# Y2.net
KiCad netlist of a schematic drawn in Altium Designer
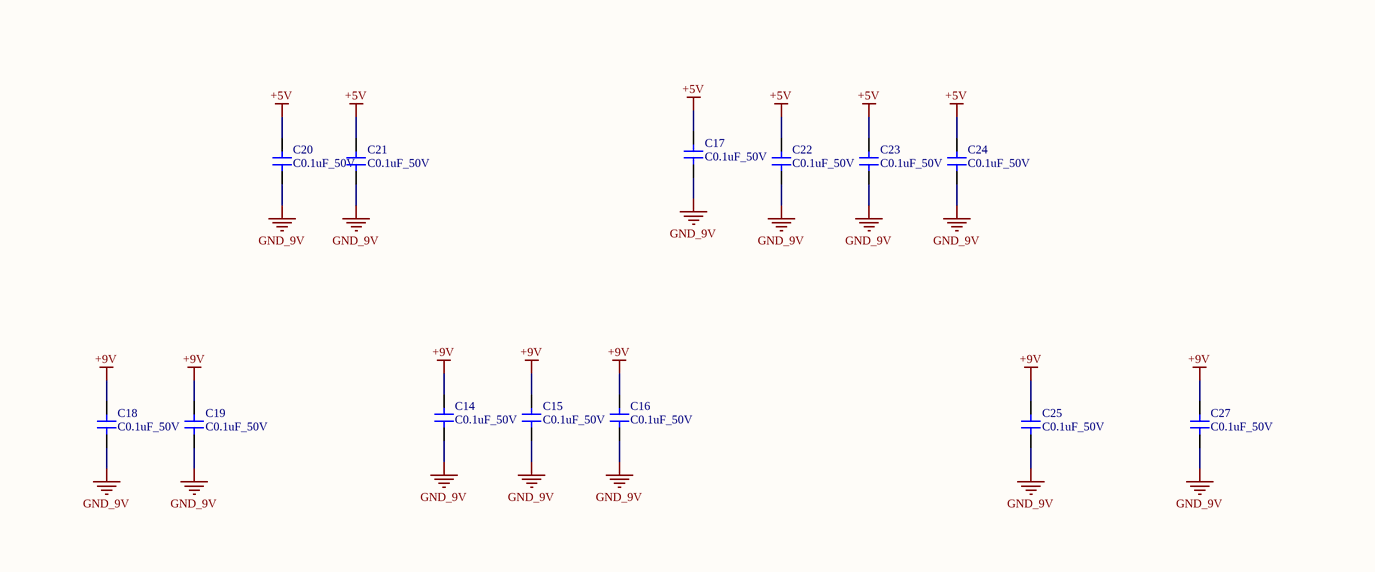
[diagram p0: Y2.SchDoc, top left]
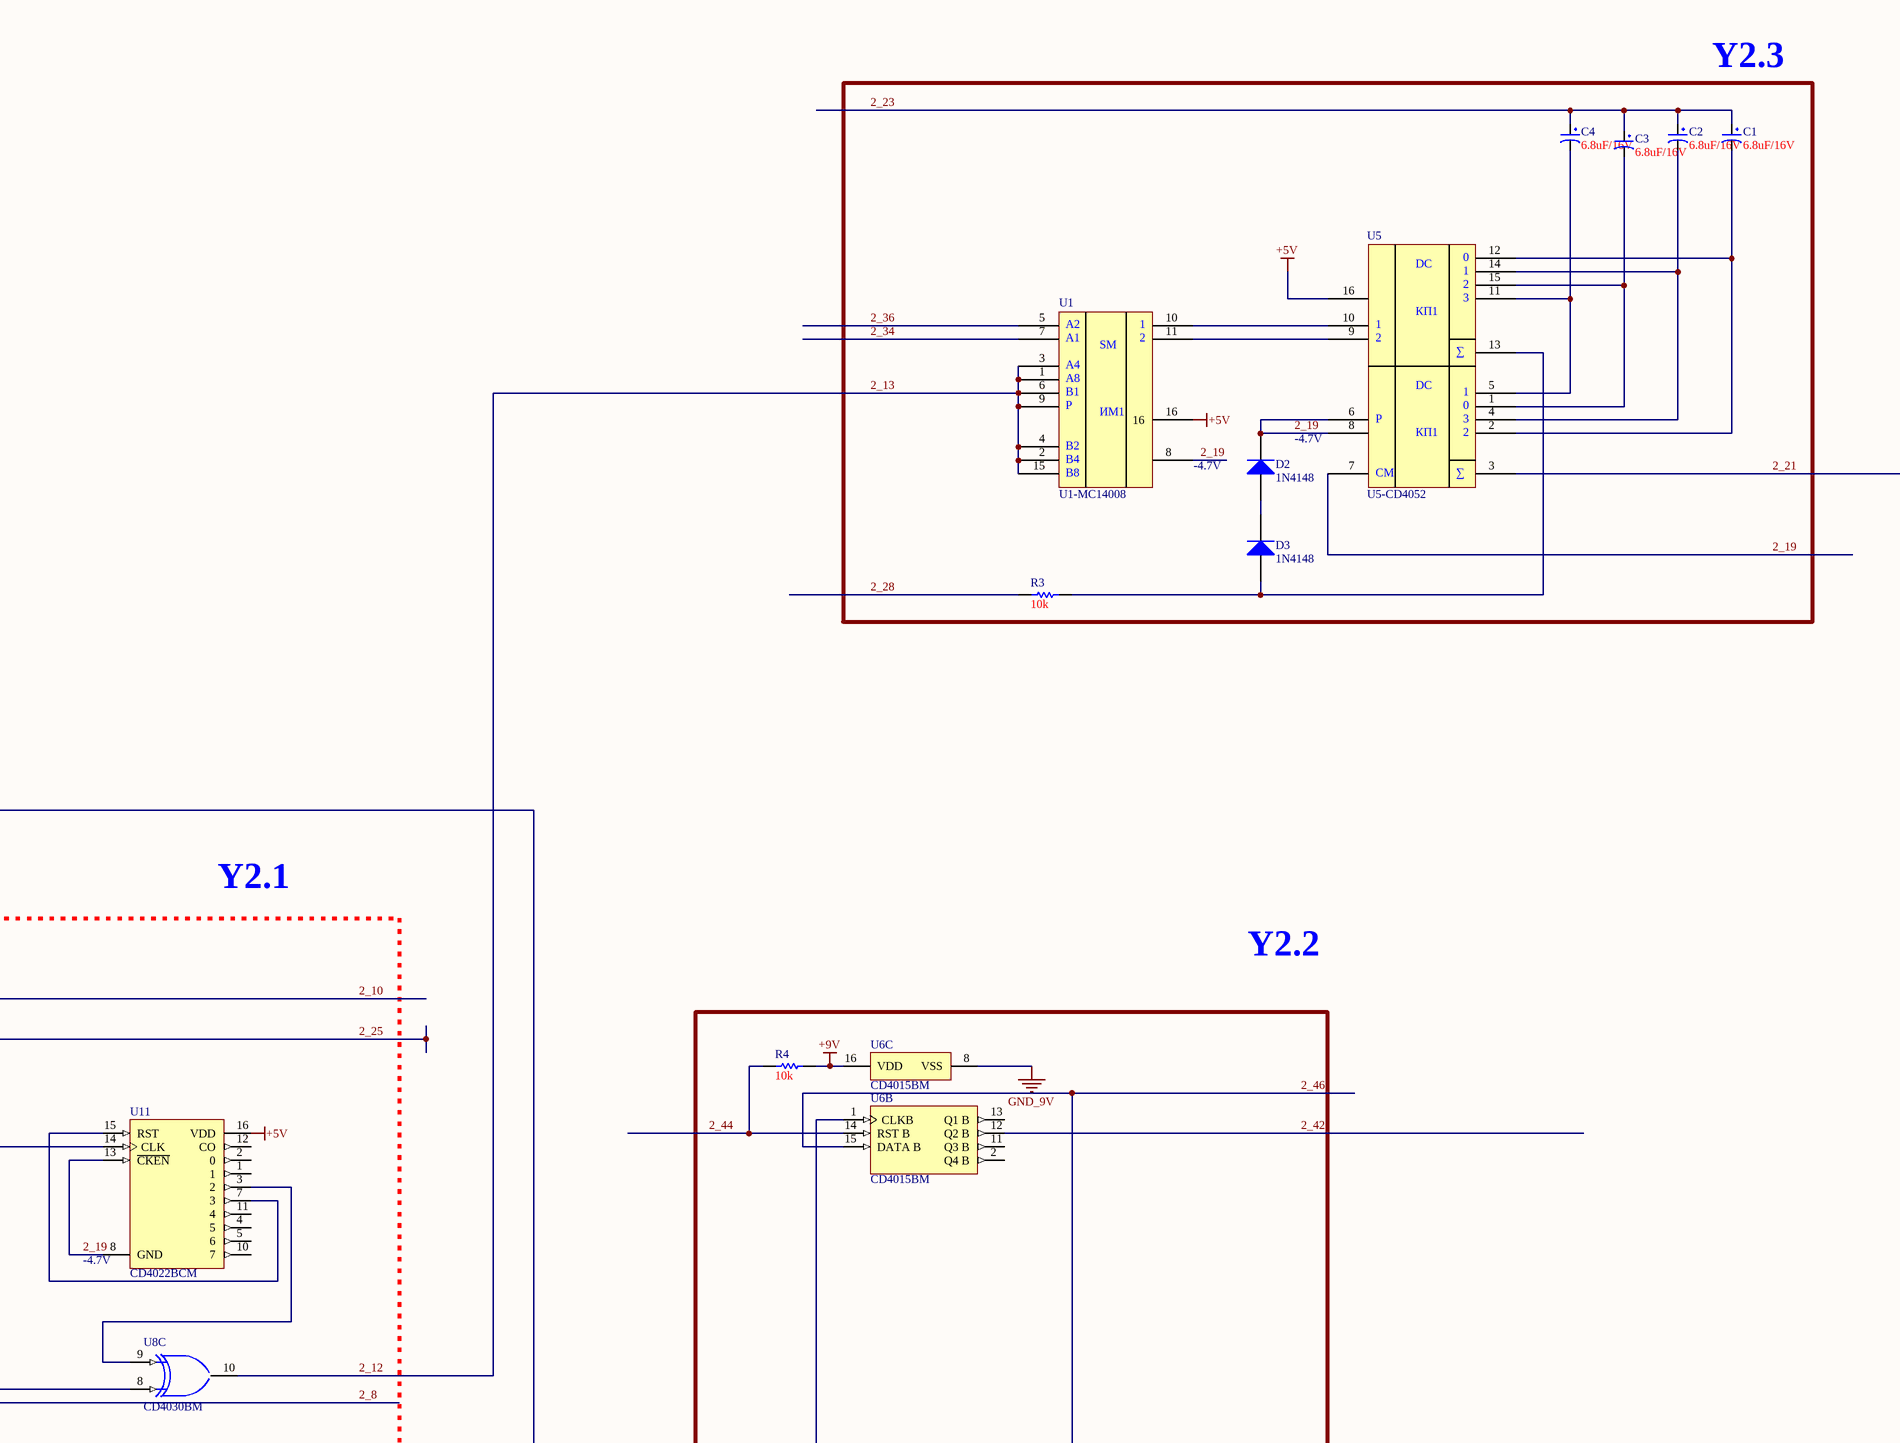
[diagram p1: Y2.SchDoc, top right]
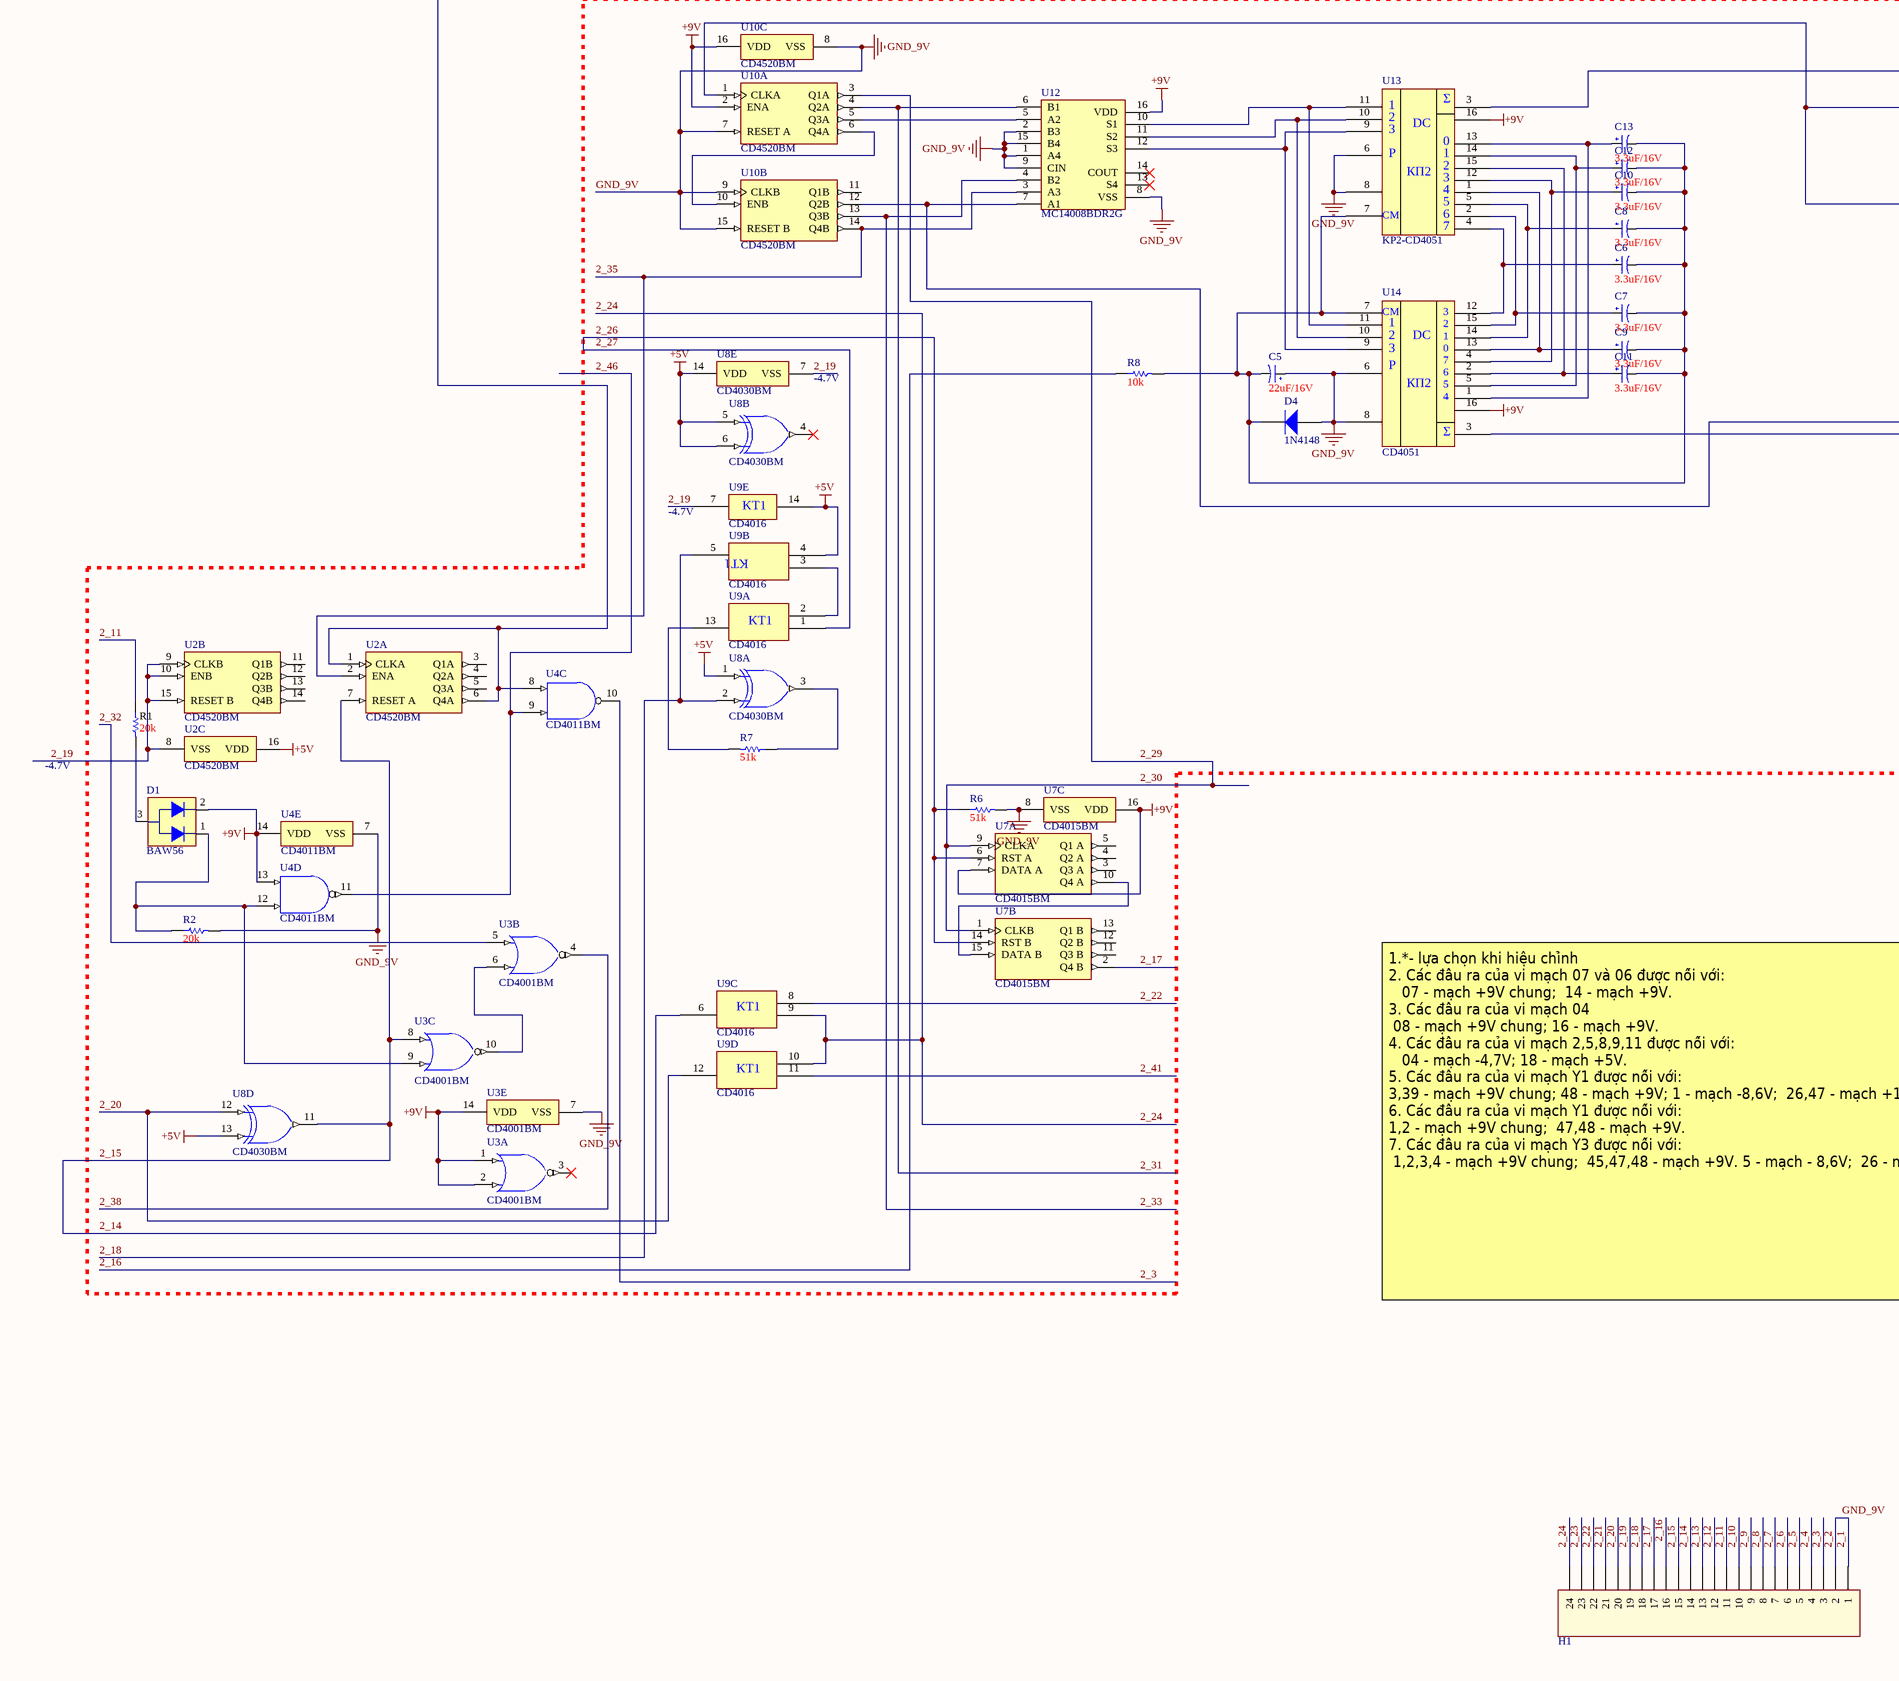
[diagram p2: Y2.SchDoc, bottom left]
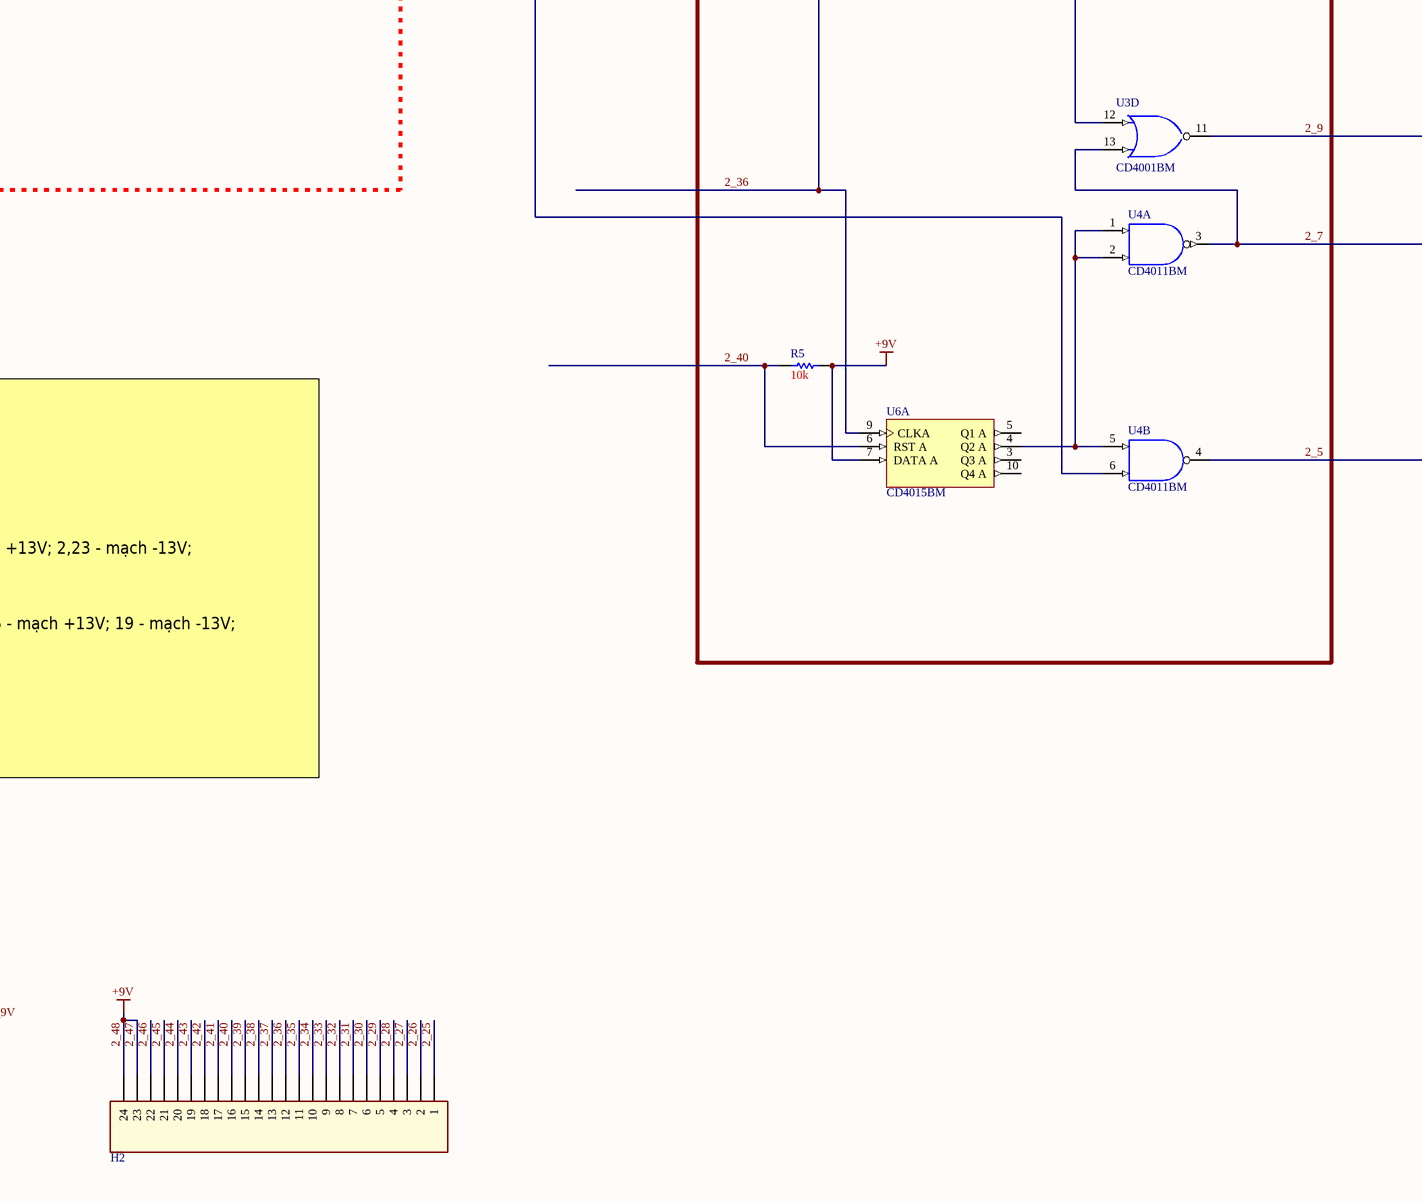
[diagram p3: Y2.SchDoc, bottom right]

(export (version "E")
  (design (tool "Eeschema 10.0.6"))
  (components
    (comp (ref "C1")
      (value "6.8uF/16V")
      (footprint "3216")
      (description "C 47uF/50V , 220uF/16V")
      (libsource (lib "syhaunguyen") (part "CP2"))
    )
    (comp (ref "C2")
      (value "6.8uF/16V")
      (footprint "3216")
      (description "C 47uF/50V , 220uF/16V")
      (libsource (lib "syhaunguyen") (part "CP2"))
    )
    (comp (ref "C3")
      (value "6.8uF/16V")
      (footprint "3216")
      (description "C 47uF/50V , 220uF/16V")
      (libsource (lib "syhaunguyen") (part "CP2"))
    )
    (comp (ref "C4")
      (value "6.8uF/16V")
      (footprint "3216")
      (description "C 47uF/50V , 220uF/16V")
      (libsource (lib "syhaunguyen") (part "CP2"))
    )
    (comp (ref "C5")
      (value "22uF/16V")
      (footprint "3528")
      (description "Cap P  0,1uF < 22uF , 16 - 50V")
      (libsource (lib "syhaunguyen") (part "CP1"))
    )
    (comp (ref "C6")
      (value "3.3uF/16V")
      (footprint "3216")
      (description "Cap P  0,1uF < 22uF , 16 - 50V")
      (libsource (lib "syhaunguyen") (part "CP1"))
    )
    (comp (ref "C7")
      (value "3.3uF/16V")
      (footprint "3216")
      (description "Cap P  0,1uF < 22uF , 16 - 50V")
      (libsource (lib "syhaunguyen") (part "CP1"))
    )
    (comp (ref "C8")
      (value "3.3uF/16V")
      (footprint "3216")
      (description "Cap P  0,1uF < 22uF , 16 - 50V")
      (libsource (lib "syhaunguyen") (part "CP1"))
    )
    (comp (ref "C9")
      (value "3.3uF/16V")
      (footprint "3216")
      (description "Cap P  0,1uF < 22uF , 16 - 50V")
      (libsource (lib "syhaunguyen") (part "CP1"))
    )
    (comp (ref "C10")
      (value "3.3uF/16V")
      (footprint "3216")
      (description "Cap P  0,1uF < 22uF , 16 - 50V")
      (libsource (lib "syhaunguyen") (part "CP1"))
    )
    (comp (ref "C11")
      (value "3.3uF/16V")
      (footprint "3216")
      (description "Cap P  0,1uF < 22uF , 16 - 50V")
      (libsource (lib "syhaunguyen") (part "CP1"))
    )
    (comp (ref "C12")
      (value "3.3uF/16V")
      (footprint "3216")
      (description "Cap P  0,1uF < 22uF , 16 - 50V")
      (libsource (lib "syhaunguyen") (part "CP1"))
    )
    (comp (ref "C13")
      (value "3.3uF/16V")
      (footprint "3216")
      (description "Cap P  0,1uF < 22uF , 16 - 50V")
      (libsource (lib "syhaunguyen") (part "CP1"))
    )
    (comp (ref "C14")
      (value "C0.1uF_50V")
      (footprint "Masterit1805:C0805")
      (libsource (lib "AMK") (part "C0.1uF_50V"))
    )
    (comp (ref "C15")
      (value "C0.1uF_50V")
      (footprint "Masterit1805:C0805")
      (libsource (lib "AMK") (part "C0.1uF_50V"))
    )
    (comp (ref "C16")
      (value "C0.1uF_50V")
      (footprint "Masterit1805:C0805")
      (libsource (lib "AMK") (part "C0.1uF_50V"))
    )
    (comp (ref "C17")
      (value "C0.1uF_50V")
      (footprint "Masterit1805:C0805")
      (libsource (lib "AMK") (part "C0.1uF_50V"))
    )
    (comp (ref "C18")
      (value "C0.1uF_50V")
      (footprint "Masterit1805:C0805")
      (libsource (lib "AMK") (part "C0.1uF_50V"))
    )
    (comp (ref "C19")
      (value "C0.1uF_50V")
      (footprint "Masterit1805:C0805")
      (libsource (lib "AMK") (part "C0.1uF_50V"))
    )
    (comp (ref "C20")
      (value "C0.1uF_50V")
      (footprint "Masterit1805:C0805")
      (libsource (lib "AMK") (part "C0.1uF_50V"))
    )
    (comp (ref "C21")
      (value "C0.1uF_50V")
      (footprint "Masterit1805:C0805")
      (libsource (lib "AMK") (part "C0.1uF_50V"))
    )
    (comp (ref "C22")
      (value "C0.1uF_50V")
      (footprint "Masterit1805:C0805")
      (libsource (lib "AMK") (part "C0.1uF_50V"))
    )
    (comp (ref "C23")
      (value "C0.1uF_50V")
      (footprint "Masterit1805:C0805")
      (libsource (lib "AMK") (part "C0.1uF_50V"))
    )
    (comp (ref "C24")
      (value "C0.1uF_50V")
      (footprint "Masterit1805:C0805")
      (libsource (lib "AMK") (part "C0.1uF_50V"))
    )
    (comp (ref "C25")
      (value "C0.1uF_50V")
      (footprint "Masterit1805:C0805")
      (libsource (lib "AMK") (part "C0.1uF_50V"))
    )
    (comp (ref "C27")
      (value "C0.1uF_50V")
      (footprint "Masterit1805:C0805")
      (libsource (lib "AMK") (part "C0.1uF_50V"))
    )
    (comp (ref "D1") (value "BAW56") (footprint "sot-23") (libsource (lib "27V-30A") (part "UF3")))
    (comp (ref "D2")
      (value "1N4148")
      (footprint "SOD123")
      (description "Dán")
      (libsource (lib "Altium_Lib_by_KhueNguyenCreator") (part "Diode S4"))
    )
    (comp (ref "D3")
      (value "1N4148")
      (footprint "SOD123")
      (description "Dán")
      (libsource (lib "Altium_Lib_by_KhueNguyenCreator") (part "Diode S4"))
    )
    (comp (ref "D4")
      (value "1N4148")
      (footprint "SOD123")
      (description "Dán")
      (libsource (lib "Altium_Lib_by_KhueNguyenCreator") (part "Diode S4"))
    )
    (comp (ref "H1")
      (value "Header 24")
      (footprint "header 24")
      (libsource (lib "LIB_EMBEDDED1805") (part "Header 24"))
    )
    (comp (ref "H2")
      (value "Header 24")
      (footprint "header 24")
      (libsource (lib "LIB_EMBEDDED1805") (part "Header 24"))
    )
    (comp (ref "R1")
      (value "20k")
      (footprint "R0805")
      (description "Standard resistor")
      (fields (field (name "ASID PART NUMBER") "Res-AS"))
      (libsource (lib "Mylib+Rev+4") (part "Res"))
    )
    (comp (ref "R2")
      (value "20k")
      (footprint "R0805")
      (description "Standard resistor")
      (fields (field (name "ASID PART NUMBER") "Res-AS"))
      (libsource (lib "Mylib+Rev+4") (part "Res"))
    )
    (comp (ref "R3")
      (value "10k")
      (footprint "Masterit1805:C0805")
      (description "Standard resistor")
      (fields (field (name "ASID PART NUMBER") "Res-AS"))
      (libsource (lib "Mylib+Rev+4") (part "Res"))
    )
    (comp (ref "R4")
      (value "10k")
      (footprint "R0805")
      (description "Standard resistor")
      (fields (field (name "ASID PART NUMBER") "Res-AS"))
      (libsource (lib "Mylib+Rev+4") (part "Res"))
    )
    (comp (ref "R5")
      (value "10k")
      (footprint "R0805")
      (description "Standard resistor")
      (fields (field (name "ASID PART NUMBER") "Res-AS"))
      (libsource (lib "Mylib+Rev+4") (part "Res"))
    )
    (comp (ref "R6")
      (value "51k")
      (footprint "R0805")
      (description "Standard resistor")
      (fields (field (name "ASID PART NUMBER") "Res-AS"))
      (libsource (lib "Mylib+Rev+4") (part "Res"))
    )
    (comp (ref "R7")
      (value "51k")
      (footprint "Masterit1805:C0805")
      (description "Standard resistor")
      (fields (field (name "ASID PART NUMBER") "Res-AS"))
      (libsource (lib "Mylib+Rev+4") (part "Res"))
    )
    (comp (ref "R8")
      (value "10k")
      (footprint "1206")
      (description "Standard resistor")
      (fields (field (name "ASID PART NUMBER") "Res-AS"))
      (libsource (lib "Mylib+Rev+4") (part "Res"))
    )
    (comp (ref "U1")
      (value "U1-MC14008")
      (footprint "soic16n")
      (libsource (lib "LIB_OF_PHONG") (part "U1-MC14008"))
    )
    (comp (ref "U2")
      (value "CD4520BM")
      (footprint "D0016A_N")
      (description "CMOS Dual Binary Up-Counter, D0016A, TUBE")
      (fields
        (field (name "GENERIC PART NUMBER") "CD4520B")
        (field (name "MANUFACTURER") "Texas Instruments")
      )
      (libsource (lib "TI_Logic_Specialty_Logic") (part "CD4520BM"))
    )
    (comp (ref "U3")
      (value "CD4001BM")
      (footprint "D0014A_N")
      (description "CMOS Quad 2-Input NOR Gate, D0014A, TUBE")
      (fields
        (field (name "GENERIC PART NUMBER") "CD4001B")
        (field (name "MANUFACTURER") "Texas Instruments")
      )
      (libsource (lib "TI_Logic_Gate") (part "CD4001BM"))
    )
    (comp (ref "U4")
      (value "CD4011BM")
      (footprint "D0014A_N")
      (description "CMOS Quad 2-Input NAND Gate, D0014A, TUBE")
      (fields
        (field (name "GENERIC PART NUMBER") "CD4011B")
        (field (name "MANUFACTURER") "Texas Instruments")
      )
      (libsource (lib "TI_Logic_Gate") (part "CD4011BM"))
    )
    (comp (ref "U5")
      (value "U5-CD4052")
      (footprint "soic16n")
      (libsource (lib "LIB_OF_PHONG") (part "U5-CD4052"))
    )
    (comp (ref "U6")
      (value "CD4015BM")
      (footprint "D0016A_N")
      (description "CMOS Dual 4-Stage Static Shift Register, D0016A, TUBE")
      (fields
        (field (name "GENERIC PART NUMBER") "CD4015B")
        (field (name "MANUFACTURER") "Texas Instruments")
      )
      (libsource (lib "TI_Logic_Flip-Flop,Latch,Register") (part "CD4015BM"))
    )
    (comp (ref "U7")
      (value "CD4015BM")
      (footprint "D0016A_N")
      (description "CMOS Dual 4-Stage Static Shift Register, D0016A, TUBE")
      (fields
        (field (name "GENERIC PART NUMBER") "CD4015B")
        (field (name "MANUFACTURER") "Texas Instruments")
      )
      (libsource (lib "") (part "CD4015BM_1"))
    )
    (comp (ref "U8")
      (value "CD4030BM")
      (footprint "D0014A_N")
      (description "CMOS Quad Exclusive-OR Gate, D0014A, TUBE")
      (fields
        (field (name "GENERIC PART NUMBER") "CD4030B")
        (field (name "MANUFACTURER") "Texas Instruments")
      )
      (libsource (lib "TI_Logic_Gate") (part "CD4030BM"))
    )
    (comp (ref "U9") (value "CD4016") (footprint "SOIC14") (libsource (lib "LIB_OF_PHONG") (part "CD4016")))
    (comp (ref "U10")
      (value "CD4520BM")
      (footprint "D0016A_N")
      (description "CMOS Dual Binary Up-Counter, D0016A, TUBE")
      (fields
        (field (name "GENERIC PART NUMBER") "CD4520B")
        (field (name "MANUFACTURER") "Texas Instruments")
      )
      (libsource (lib "") (part "CD4520BM_1"))
    )
    (comp (ref "U11")
      (value "CD4022BCM")
      (footprint "SOP16")
      (description "Divide by 8 Counter/Divider with 8 Decoded Outputs")
      (fields (field (name "PUBLISHER") "Altium Limited"))
      (libsource (lib "FSC Logic Counter") (part "CD4022BCM"))
    )
    (comp (ref "U12")
      (value "MC14008BDR2G")
      (footprint "SamacSys:SOIC127P600X175-16N")
      (description "THAY THẾ CD4008")
      (fields (field (name "MOUSER PART NUMBER") "863-MC14008BDR2G"))
      (libsource (lib "*") (part "MC14008BDR2G"))
    )
    (comp (ref "U13")
      (value "KP2-CD4051")
      (footprint "soic16n")
      (libsource (lib "LIB_OF_PHONG") (part "KP2-CD4051"))
    )
    (comp (ref "U14") (value "CD4051") (footprint "soic16n") (libsource (lib "LIB_OF_PHONG") (part "CD4051")))
  )
  (nets
    (net (code "1") (name "+5V") (class "Default")
      (node (ref "C17") (pin "2") (pinfunction "2_2") (pintype "passive"))
      (node (ref "C20") (pin "2") (pinfunction "2_2") (pintype "passive"))
      (node (ref "C21") (pin "2") (pinfunction "2_2") (pintype "passive"))
      (node (ref "C22") (pin "2") (pinfunction "2_2") (pintype "passive"))
      (node (ref "C23") (pin "2") (pinfunction "2_2") (pintype "passive"))
      (node (ref "C24") (pin "2") (pinfunction "2_2") (pintype "passive"))
      (node (ref "U1") (pin "16") (pinfunction "16_16") (pintype "passive"))
      (node (ref "U11") (pin "16") (pinfunction "VDD_16") (pintype "power_in"))
      (node (ref "U2") (pin "16") (pinfunction "VDD_16") (pintype "power_in"))
      (node (ref "U5") (pin "16") (pinfunction "16_16") (pintype "passive"))
      (node (ref "U8") (pin "1") (pinfunction "A_1") (pintype "input"))
      (node (ref "U8") (pin "13") (pinfunction "H_13") (pintype "input"))
      (node (ref "U8") (pin "14") (pinfunction "VDD_14") (pintype "power_in"))
      (node (ref "U8") (pin "5") (pinfunction "C_5") (pintype "input"))
      (node (ref "U8") (pin "6") (pinfunction "D_6") (pintype "input"))
      (node (ref "U9") (pin "14") (pinfunction "14_14") (pintype "passive"))
      (node (ref "U9") (pin "4") (pinfunction "4_4") (pintype "passive"))
    )
    (net (code "2") (name "+9V") (class "Default")
      (node (ref "C14") (pin "2") (pinfunction "2_2") (pintype "passive"))
      (node (ref "C15") (pin "2") (pinfunction "2_2") (pintype "passive"))
      (node (ref "C16") (pin "2") (pinfunction "2_2") (pintype "passive"))
      (node (ref "C18") (pin "2") (pinfunction "2_2") (pintype "passive"))
      (node (ref "C19") (pin "2") (pinfunction "2_2") (pintype "passive"))
      (node (ref "C25") (pin "2") (pinfunction "2_2") (pintype "passive"))
      (node (ref "C27") (pin "2") (pinfunction "2_2") (pintype "passive"))
      (node (ref "D1") (pin "2") (pinfunction "2_2") (pintype "passive"))
      (node (ref "H2") (pin "23") (pinfunction "23_23") (pintype "passive"))
      (node (ref "H2") (pin "24") (pinfunction "24_24") (pintype "passive"))
      (node (ref "R4") (pin "2") (pinfunction "2_2") (pintype "passive"))
      (node (ref "R5") (pin "1") (pinfunction "1_1") (pintype "passive"))
      (node (ref "U10") (pin "16") (pinfunction "VDD_16") (pintype "power_in"))
      (node (ref "U10") (pin "2") (pinfunction "ENA_2") (pintype "input"))
      (node (ref "U12") (pin "16") (pinfunction "VDD_16") (pintype "passive"))
      (node (ref "U13") (pin "16") (pinfunction "16_16") (pintype "passive"))
      (node (ref "U14") (pin "16") (pinfunction "16_16") (pintype "passive"))
      (node (ref "U3") (pin "1") (pinfunction "A_1") (pintype "input"))
      (node (ref "U3") (pin "14") (pinfunction "VDD_14") (pintype "power_in"))
      (node (ref "U3") (pin "2") (pinfunction "B_2") (pintype "input"))
      (node (ref "U4") (pin "13") (pinfunction "H_13") (pintype "input"))
      (node (ref "U4") (pin "14") (pinfunction "VDD_14") (pintype "power_in"))
      (node (ref "U6") (pin "16") (pinfunction "VDD_16") (pintype "power_in"))
      (node (ref "U6") (pin "7") (pinfunction "DATA_A_7") (pintype "input"))
      (node (ref "U7") (pin "16") (pinfunction "VDD_16") (pintype "power_in"))
      (node (ref "U7") (pin "7") (pinfunction "DATA_A_7") (pintype "input"))
    )
    (net (code "3") (name "/2_3") (class "Default")
      (node (ref "H1") (pin "3") (pinfunction "3_3") (pintype "passive"))
      (node (ref "U4") (pin "10") (pinfunction "L_10") (pintype "passive"))
    )
    (net (code "4") (name "/2_4") (class "Default")
      (node (ref "H1") (pin "4") (pinfunction "4_4") (pintype "passive"))
    )
    (net (code "5") (name "/2_5") (class "Default")
      (node (ref "H1") (pin "5") (pinfunction "5_5") (pintype "passive"))
      (node (ref "U4") (pin "4") (pinfunction "K_4") (pintype "output"))
    )
    (net (code "6") (name "/2_6") (class "Default")
      (node (ref "H1") (pin "6") (pinfunction "6_6") (pintype "passive"))
    )
    (net (code "7") (name "/2_7") (class "Default")
      (node (ref "H1") (pin "7") (pinfunction "7_7") (pintype "passive"))
      (node (ref "U3") (pin "13") (pinfunction "H_13") (pintype "input"))
      (node (ref "U4") (pin "3") (pinfunction "J_3") (pintype "output"))
    )
    (net (code "8") (name "/2_8") (class "Default")
      (node (ref "H1") (pin "8") (pinfunction "8_8") (pintype "passive"))
      (node (ref "U14") (pin "3") (pinfunction "3_3") (pintype "passive"))
    )
    (net (code "9") (name "/2_9") (class "Default")
      (node (ref "H1") (pin "9") (pinfunction "9_9") (pintype "passive"))
      (node (ref "U3") (pin "11") (pinfunction "M_11") (pintype "output"))
    )
    (net (code "10") (name "/2_10") (class "Default")
      (node (ref "H1") (pin "10") (pinfunction "10_10") (pintype "passive"))
      (node (ref "U13") (pin "3") (pinfunction "3_3") (pintype "passive"))
    )
    (net (code "11") (name "/2_11") (class "Default")
      (node (ref "H1") (pin "11") (pinfunction "11_11") (pintype "passive"))
      (node (ref "R1") (pin "1") (pinfunction "1_1") (pintype "passive"))
    )
    (net (code "12") (name "/2_12") (class "Default")
      (node (ref "H1") (pin "12") (pinfunction "12_12") (pintype "passive"))
      (node (ref "H1") (pin "13") (pinfunction "13_13") (pintype "passive"))
      (node (ref "U1") (pin "1") (pinfunction "1_1") (pintype "passive"))
      (node (ref "U1") (pin "15") (pinfunction "15_15") (pintype "passive"))
      (node (ref "U1") (pin "2") (pinfunction "2_2") (pintype "passive"))
      (node (ref "U1") (pin "3") (pinfunction "3_3") (pintype "passive"))
      (node (ref "U1") (pin "4") (pinfunction "4_4") (pintype "passive"))
      (node (ref "U1") (pin "6") (pinfunction "6_6") (pintype "passive"))
      (node (ref "U1") (pin "9") (pinfunction "9_9") (pintype "passive"))
      (node (ref "U8") (pin "10") (pinfunction "L_10") (pintype "passive"))
    )
    (net (code "13") (name "/2_14") (class "Default")
      (node (ref "H1") (pin "14") (pinfunction "14_14") (pintype "passive"))
      (node (ref "H1") (pin "15") (pinfunction "15_15") (pintype "passive"))
      (node (ref "U2") (pin "7") (pinfunction "RESET_A_7") (pintype "input"))
      (node (ref "U3") (pin "8") (pinfunction "E_8") (pintype "input"))
      (node (ref "U8") (pin "11") (pinfunction "M_11") (pintype "output"))
      (node (ref "U9") (pin "6") (pinfunction "6_6") (pintype "passive"))
    )
    (net (code "14") (name "/2_16") (class "Default")
      (node (ref "H1") (pin "16") (pinfunction "16_16") (pintype "passive"))
      (node (ref "R8") (pin "1") (pinfunction "1_1") (pintype "passive"))
    )
    (net (code "15") (name "/2_17") (class "Default")
      (node (ref "H1") (pin "17") (pinfunction "17_17") (pintype "passive"))
      (node (ref "U7") (pin "2") (pinfunction "Q4_B_2") (pintype "output"))
    )
    (net (code "16") (name "/2_18") (class "Default")
      (node (ref "H1") (pin "18") (pinfunction "18_18") (pintype "passive"))
      (node (ref "U8") (pin "2") (pinfunction "B_2") (pintype "input"))
      (node (ref "U9") (pin "5") (pinfunction "5_5") (pintype "passive"))
    )
    (net (code "17") (name "/2_19") (class "Default")
      (node (ref "D2") (pin "2") (pinfunction "K_2") (pintype "passive"))
      (node (ref "H1") (pin "19") (pinfunction "19_19") (pintype "passive"))
      (node (ref "U1") (pin "8") (pinfunction "8_8") (pintype "passive"))
      (node (ref "U11") (pin "13") (pinfunction "~{CKEN}_13") (pintype "input"))
      (node (ref "U11") (pin "8") (pinfunction "GND_8") (pintype "power_in"))
      (node (ref "U2") (pin "10") (pinfunction "ENB_10") (pintype "input"))
      (node (ref "U2") (pin "15") (pinfunction "RESET_B_15") (pintype "input"))
      (node (ref "U2") (pin "8") (pinfunction "VSS_8") (pintype "power_in"))
      (node (ref "U2") (pin "9") (pinfunction "CLKB_9") (pintype "input"))
      (node (ref "U5") (pin "6") (pinfunction "6_6") (pintype "passive"))
      (node (ref "U5") (pin "7") (pinfunction "7_7") (pintype "passive"))
      (node (ref "U5") (pin "8") (pinfunction "8_8") (pintype "passive"))
      (node (ref "U8") (pin "7") (pinfunction "VSS_7") (pintype "power_in"))
      (node (ref "U9") (pin "7") (pinfunction "7_7") (pintype "passive"))
    )
    (net (code "18") (name "/2_20") (class "Default")
      (node (ref "H1") (pin "20") (pinfunction "20_20") (pintype "passive"))
      (node (ref "U8") (pin "12") (pinfunction "G_12") (pintype "input"))
      (node (ref "U9") (pin "12") (pinfunction "12_12") (pintype "passive"))
    )
    (net (code "19") (name "/2_21") (class "Default")
      (node (ref "H1") (pin "21") (pinfunction "21_21") (pintype "passive"))
      (node (ref "U5") (pin "3") (pinfunction "3_3") (pintype "passive"))
    )
    (net (code "20") (name "/2_22") (class "Default")
      (node (ref "H1") (pin "22") (pinfunction "22_22") (pintype "passive"))
      (node (ref "U9") (pin "8") (pinfunction "8_8") (pintype "passive"))
    )
    (net (code "21") (name "/2_23") (class "Default")
      (node (ref "C1") (pin "1") (pinfunction "1_1") (pintype "passive"))
      (node (ref "C2") (pin "1") (pinfunction "1_1") (pintype "passive"))
      (node (ref "C3") (pin "1") (pinfunction "1_1") (pintype "passive"))
      (node (ref "C4") (pin "1") (pinfunction "1_1") (pintype "passive"))
      (node (ref "H1") (pin "23") (pinfunction "23_23") (pintype "passive"))
    )
    (net (code "22") (name "/2_24") (class "Default")
      (node (ref "H1") (pin "24") (pinfunction "24_24") (pintype "passive"))
      (node (ref "U9") (pin "10") (pinfunction "10_10") (pintype "passive"))
      (node (ref "U9") (pin "9") (pinfunction "9_9") (pintype "passive"))
    )
    (net (code "23") (name "/2_25") (class "Default")
      (node (ref "H2") (pin "1") (pinfunction "1_1") (pintype "passive"))
      (node (ref "U10") (pin "1") (pinfunction "CLKA_1") (pintype "input"))
      (node (ref "U11") (pin "14") (pinfunction "CLK_14") (pintype "input"))
    )
    (net (code "24") (name "/2_26") (class "Default")
      (node (ref "H2") (pin "2") (pinfunction "2_2") (pintype "passive"))
      (node (ref "H2") (pin "3") (pinfunction "3_3") (pintype "passive"))
      (node (ref "R6") (pin "1") (pinfunction "1_1") (pintype "passive"))
      (node (ref "U7") (pin "14") (pinfunction "RST_B_14") (pintype "input"))
      (node (ref "U7") (pin "6") (pinfunction "RST_A_6") (pintype "input"))
      (node (ref "U9") (pin "1") (pinfunction "1_1") (pintype "passive"))
    )
    (net (code "25") (name "/2_28") (class "Default")
      (node (ref "H2") (pin "4") (pinfunction "4_4") (pintype "passive"))
      (node (ref "R3") (pin "2") (pinfunction "2_2") (pintype "passive"))
    )
    (net (code "26") (name "/2_29") (class "Default")
      (node (ref "H2") (pin "5") (pinfunction "5_5") (pintype "passive"))
      (node (ref "H2") (pin "6") (pinfunction "6_6") (pintype "passive"))
      (node (ref "U10") (pin "3") (pinfunction "Q1A_3") (pintype "output"))
      (node (ref "U7") (pin "1") (pinfunction "CLKB_1") (pintype "input"))
      (node (ref "U7") (pin "9") (pinfunction "CLKA_9") (pintype "input"))
    )
    (net (code "27") (name "/2_31") (class "Default")
      (node (ref "H2") (pin "7") (pinfunction "7_7") (pintype "passive"))
      (node (ref "U10") (pin "4") (pinfunction "Q2A_4") (pintype "output"))
      (node (ref "U12") (pin "6") (pinfunction "B1_6") (pintype "passive"))
    )
    (net (code "28") (name "/2_32") (class "Default")
      (node (ref "H2") (pin "8") (pinfunction "8_8") (pintype "passive"))
      (node (ref "U3") (pin "5") (pinfunction "C_5") (pintype "input"))
    )
    (net (code "29") (name "/2_33") (class "Default")
      (node (ref "H2") (pin "9") (pinfunction "9_9") (pintype "passive"))
      (node (ref "U10") (pin "13") (pinfunction "Q3B_13") (pintype "output"))
      (node (ref "U12") (pin "4") (pinfunction "B2_4") (pintype "passive"))
    )
    (net (code "30") (name "/2_34") (class "Default")
      (node (ref "H2") (pin "10") (pinfunction "10_10") (pintype "passive"))
      (node (ref "U1") (pin "7") (pinfunction "7_7") (pintype "passive"))
    )
    (net (code "31") (name "/2_35") (class "Default")
      (node (ref "H2") (pin "11") (pinfunction "11_11") (pintype "passive"))
      (node (ref "U10") (pin "14") (pinfunction "Q4B_14") (pintype "output"))
      (node (ref "U12") (pin "3") (pinfunction "A3_3") (pintype "passive"))
      (node (ref "U2") (pin "2") (pinfunction "ENA_2") (pintype "input"))
    )
    (net (code "32") (name "/2_36") (class "Default")
      (node (ref "H2") (pin "12") (pinfunction "12_12") (pintype "passive"))
      (node (ref "U1") (pin "5") (pinfunction "5_5") (pintype "passive"))
      (node (ref "U6") (pin "1") (pinfunction "CLKB_1") (pintype "input"))
      (node (ref "U6") (pin "9") (pinfunction "CLKA_9") (pintype "input"))
    )
    (net (code "33") (name "/2_37") (class "Default")
      (node (ref "H2") (pin "13") (pinfunction "13_13") (pintype "passive"))
    )
    (net (code "34") (name "/2_38") (class "Default")
      (node (ref "H2") (pin "14") (pinfunction "14_14") (pintype "passive"))
      (node (ref "U3") (pin "4") (pinfunction "K_4") (pintype "output"))
    )
    (net (code "35") (name "/2_39") (class "Default")
      (node (ref "H2") (pin "15") (pinfunction "15_15") (pintype "passive"))
    )
    (net (code "36") (name "/2_40") (class "Default")
      (node (ref "H2") (pin "16") (pinfunction "16_16") (pintype "passive"))
      (node (ref "R5") (pin "2") (pinfunction "2_2") (pintype "passive"))
      (node (ref "U6") (pin "6") (pinfunction "RST_A_6") (pintype "input"))
    )
    (net (code "37") (name "/2_41") (class "Default")
      (node (ref "H2") (pin "17") (pinfunction "17_17") (pintype "passive"))
      (node (ref "U9") (pin "11") (pinfunction "11_11") (pintype "passive"))
    )
    (net (code "38") (name "/2_42") (class "Default")
      (node (ref "H2") (pin "18") (pinfunction "18_18") (pintype "passive"))
      (node (ref "U6") (pin "12") (pinfunction "Q2_B_12") (pintype "output"))
    )
    (net (code "39") (name "/2_43") (class "Default")
      (node (ref "H2") (pin "19") (pinfunction "19_19") (pintype "passive"))
    )
    (net (code "40") (name "/2_44") (class "Default")
      (node (ref "H2") (pin "20") (pinfunction "20_20") (pintype "passive"))
      (node (ref "R4") (pin "1") (pinfunction "1_1") (pintype "passive"))
      (node (ref "U6") (pin "14") (pinfunction "RST_B_14") (pintype "input"))
    )
    (net (code "41") (name "/2_45") (class "Default")
      (node (ref "H2") (pin "21") (pinfunction "21_21") (pintype "passive"))
    )
    (net (code "42") (name "/2_46") (class "Default")
      (node (ref "H2") (pin "22") (pinfunction "22_22") (pintype "passive"))
      (node (ref "U3") (pin "12") (pinfunction "G_12") (pintype "input"))
      (node (ref "U4") (pin "11") (pinfunction "M_11") (pintype "output"))
      (node (ref "U4") (pin "9") (pinfunction "F_9") (pintype "input"))
      (node (ref "U6") (pin "15") (pinfunction "DATA_B_15") (pintype "input"))
    )
    (net (code "43") (name "GND_9V") (class "Default")
      (node (ref "C14") (pin "1") (pinfunction "1_1") (pintype "passive"))
      (node (ref "C15") (pin "1") (pinfunction "1_1") (pintype "passive"))
      (node (ref "C16") (pin "1") (pinfunction "1_1") (pintype "passive"))
      (node (ref "C17") (pin "1") (pinfunction "1_1") (pintype "passive"))
      (node (ref "C18") (pin "1") (pinfunction "1_1") (pintype "passive"))
      (node (ref "C19") (pin "1") (pinfunction "1_1") (pintype "passive"))
      (node (ref "C20") (pin "1") (pinfunction "1_1") (pintype "passive"))
      (node (ref "C21") (pin "1") (pinfunction "1_1") (pintype "passive"))
      (node (ref "C22") (pin "1") (pinfunction "1_1") (pintype "passive"))
      (node (ref "C23") (pin "1") (pinfunction "1_1") (pintype "passive"))
      (node (ref "C24") (pin "1") (pinfunction "1_1") (pintype "passive"))
      (node (ref "C25") (pin "1") (pinfunction "1_1") (pintype "passive"))
      (node (ref "C27") (pin "1") (pinfunction "1_1") (pintype "passive"))
      (node (ref "C5") (pin "1") (pinfunction "1_1") (pintype "passive"))
      (node (ref "D4") (pin "1") (pinfunction "A_1") (pintype "passive"))
      (node (ref "H1") (pin "1") (pinfunction "1_1") (pintype "passive"))
      (node (ref "H1") (pin "2") (pinfunction "2_2") (pintype "passive"))
      (node (ref "R2") (pin "2") (pinfunction "2_2") (pintype "passive"))
      (node (ref "R6") (pin "2") (pinfunction "2_2") (pintype "passive"))
      (node (ref "U10") (pin "15") (pinfunction "RESET_B_15") (pintype "input"))
      (node (ref "U10") (pin "7") (pinfunction "RESET_A_7") (pintype "input"))
      (node (ref "U10") (pin "8") (pinfunction "VSS_8") (pintype "power_in"))
      (node (ref "U10") (pin "9") (pinfunction "CLKB_9") (pintype "input"))
      (node (ref "U12") (pin "1") (pinfunction "A4_1") (pintype "passive"))
      (node (ref "U12") (pin "15") (pinfunction "B4_15") (pintype "passive"))
      (node (ref "U12") (pin "2") (pinfunction "B3_2") (pintype "passive"))
      (node (ref "U12") (pin "8") (pinfunction "VSS_8") (pintype "passive"))
      (node (ref "U12") (pin "9") (pinfunction "CIN_9") (pintype "passive"))
      (node (ref "U13") (pin "6") (pinfunction "6_6") (pintype "passive"))
      (node (ref "U13") (pin "8") (pinfunction "8_8") (pintype "passive"))
      (node (ref "U14") (pin "6") (pinfunction "6_6") (pintype "passive"))
      (node (ref "U14") (pin "8") (pinfunction "8_8") (pintype "passive"))
      (node (ref "U3") (pin "7") (pinfunction "VSS_7") (pintype "power_in"))
      (node (ref "U4") (pin "7") (pinfunction "VSS_7") (pintype "power_in"))
      (node (ref "U6") (pin "8") (pinfunction "VSS_8") (pintype "power_in"))
      (node (ref "U7") (pin "8") (pinfunction "VSS_8") (pintype "power_in"))
    )
    (net (code "44") (name "Net-(C1-Pad2)") (class "Default")
      (node (ref "C1") (pin "2") (pinfunction "2_2") (pintype "passive"))
      (node (ref "U5") (pin "12") (pinfunction "12_12") (pintype "passive"))
      (node (ref "U5") (pin "2") (pinfunction "2_2") (pintype "passive"))
    )
    (net (code "45") (name "Net-(C2-Pad2)") (class "Default")
      (node (ref "C2") (pin "2") (pinfunction "2_2") (pintype "passive"))
      (node (ref "U5") (pin "14") (pinfunction "14_14") (pintype "passive"))
      (node (ref "U5") (pin "4") (pinfunction "4_4") (pintype "passive"))
    )
    (net (code "46") (name "Net-(C3-Pad2)") (class "Default")
      (node (ref "C3") (pin "2") (pinfunction "2_2") (pintype "passive"))
      (node (ref "U5") (pin "1") (pinfunction "1_1") (pintype "passive"))
      (node (ref "U5") (pin "15") (pinfunction "15_15") (pintype "passive"))
    )
    (net (code "47") (name "Net-(C4-Pad2)") (class "Default")
      (node (ref "C4") (pin "2") (pinfunction "2_2") (pintype "passive"))
      (node (ref "U5") (pin "11") (pinfunction "11_11") (pintype "passive"))
      (node (ref "U5") (pin "5") (pinfunction "5_5") (pintype "passive"))
    )
    (net (code "48") (name "Net-(C6-Pad1)") (class "Default")
      (node (ref "C6") (pin "1") (pinfunction "1_1") (pintype "passive"))
      (node (ref "U13") (pin "4") (pinfunction "4_4") (pintype "passive"))
      (node (ref "U14") (pin "12") (pinfunction "12_12") (pintype "passive"))
    )
    (net (code "49") (name "Net-(C7-Pad1)") (class "Default")
      (node (ref "C7") (pin "1") (pinfunction "1_1") (pintype "passive"))
      (node (ref "U13") (pin "2") (pinfunction "2_2") (pintype "passive"))
      (node (ref "U14") (pin "15") (pinfunction "15_15") (pintype "passive"))
    )
    (net (code "50") (name "Net-(C8-Pad1)") (class "Default")
      (node (ref "C8") (pin "1") (pinfunction "1_1") (pintype "passive"))
      (node (ref "U13") (pin "5") (pinfunction "5_5") (pintype "passive"))
      (node (ref "U14") (pin "14") (pinfunction "14_14") (pintype "passive"))
    )
    (net (code "51") (name "Net-(C9-Pad1)") (class "Default")
      (node (ref "C9") (pin "1") (pinfunction "1_1") (pintype "passive"))
      (node (ref "U13") (pin "1") (pinfunction "1_1") (pintype "passive"))
      (node (ref "U14") (pin "13") (pinfunction "13_13") (pintype "passive"))
    )
    (net (code "52") (name "Net-(C10-Pad1)") (class "Default")
      (node (ref "C10") (pin "1") (pinfunction "1_1") (pintype "passive"))
      (node (ref "U13") (pin "12") (pinfunction "12_12") (pintype "passive"))
      (node (ref "U14") (pin "4") (pinfunction "4_4") (pintype "passive"))
    )
    (net (code "53") (name "Net-(C11-Pad1)") (class "Default")
      (node (ref "C11") (pin "1") (pinfunction "1_1") (pintype "passive"))
      (node (ref "U13") (pin "15") (pinfunction "15_15") (pintype "passive"))
      (node (ref "U14") (pin "2") (pinfunction "2_2") (pintype "passive"))
    )
    (net (code "54") (name "Net-(C12-Pad1)") (class "Default")
      (node (ref "C12") (pin "1") (pinfunction "1_1") (pintype "passive"))
      (node (ref "U13") (pin "14") (pinfunction "14_14") (pintype "passive"))
      (node (ref "U14") (pin "5") (pinfunction "5_5") (pintype "passive"))
    )
    (net (code "55") (name "Net-(C13-Pad1)") (class "Default")
      (node (ref "C13") (pin "1") (pinfunction "1_1") (pintype "passive"))
      (node (ref "U13") (pin "13") (pinfunction "13_13") (pintype "passive"))
      (node (ref "U14") (pin "1") (pinfunction "1_1") (pintype "passive"))
    )
    (net (code "56") (name "Net-(D1-Pad3)") (class "Default")
      (node (ref "D1") (pin "3") (pinfunction "3_3") (pintype "passive"))
      (node (ref "R1") (pin "2") (pinfunction "2_2") (pintype "passive"))
    )
    (net (code "57") (name "Net-(D2-A)") (class "Default")
      (node (ref "D2") (pin "1") (pinfunction "A_1") (pintype "passive"))
      (node (ref "D3") (pin "2") (pinfunction "K_2") (pintype "passive"))
    )
    (net (code "58") (name "Net-(D3-A)") (class "Default")
      (node (ref "D3") (pin "1") (pinfunction "A_1") (pintype "passive"))
      (node (ref "R3") (pin "1") (pinfunction "1_1") (pintype "passive"))
      (node (ref "U5") (pin "13") (pinfunction "13_13") (pintype "passive"))
    )
    (net (code "59") (name "Net-(D4-K)") (class "Default")
      (node (ref "C10") (pin "2") (pinfunction "2_2") (pintype "passive"))
      (node (ref "C11") (pin "2") (pinfunction "2_2") (pintype "passive"))
      (node (ref "C12") (pin "2") (pinfunction "2_2") (pintype "passive"))
      (node (ref "C13") (pin "2") (pinfunction "2_2") (pintype "passive"))
      (node (ref "C5") (pin "2") (pinfunction "2_2") (pintype "passive"))
      (node (ref "C6") (pin "2") (pinfunction "2_2") (pintype "passive"))
      (node (ref "C7") (pin "2") (pinfunction "2_2") (pintype "passive"))
      (node (ref "C8") (pin "2") (pinfunction "2_2") (pintype "passive"))
      (node (ref "C9") (pin "2") (pinfunction "2_2") (pintype "passive"))
      (node (ref "D4") (pin "2") (pinfunction "K_2") (pintype "passive"))
      (node (ref "R8") (pin "2") (pinfunction "2_2") (pintype "passive"))
      (node (ref "U13") (pin "7") (pinfunction "7_7") (pintype "passive"))
      (node (ref "U14") (pin "7") (pinfunction "7_7") (pintype "passive"))
    )
    (net (code "60") (name "Net-(R7-Pad2)") (class "Default")
      (node (ref "R7") (pin "2") (pinfunction "2_2") (pintype "passive"))
      (node (ref "U9") (pin "13") (pinfunction "13_13") (pintype "passive"))
    )
    (net (code "61") (name "Net-(U1-Pad10)") (class "Default")
      (node (ref "U1") (pin "10") (pinfunction "10_10") (pintype "passive"))
      (node (ref "U5") (pin "10") (pinfunction "10_10") (pintype "passive"))
    )
    (net (code "62") (name "Net-(U1-Pad11)") (class "Default")
      (node (ref "U1") (pin "11") (pinfunction "11_11") (pintype "passive"))
      (node (ref "U5") (pin "9") (pinfunction "9_9") (pintype "passive"))
    )
    (net (code "63") (name "Net-(U2A-CLKA)") (class "Default")
      (node (ref "U2") (pin "1") (pinfunction "CLKA_1") (pintype "input"))
      (node (ref "U2") (pin "6") (pinfunction "Q4A_6") (pintype "output"))
      (node (ref "U4") (pin "6") (pinfunction "D_6") (pintype "input"))
      (node (ref "U4") (pin "8") (pinfunction "E_8") (pintype "input"))
    )
    (net (code "64") (name "Net-(U3B-D)") (class "Default")
      (node (ref "U3") (pin "10") (pinfunction "L_10") (pintype "output"))
      (node (ref "U3") (pin "6") (pinfunction "D_6") (pintype "input"))
    )
    (net (code "65") (name "Net-(U3C-F)") (class "Default")
      (node (ref "D1") (pin "1") (pinfunction "1_1") (pintype "passive"))
      (node (ref "R2") (pin "1") (pinfunction "1_1") (pintype "passive"))
      (node (ref "U3") (pin "9") (pinfunction "F_9") (pintype "input"))
      (node (ref "U4") (pin "12") (pinfunction "G_12") (pintype "input"))
    )
    (net (code "66") (name "Net-(U4A-A)") (class "Default")
      (node (ref "U4") (pin "1") (pinfunction "A_1") (pintype "input"))
      (node (ref "U4") (pin "2") (pinfunction "B_2") (pintype "input"))
      (node (ref "U4") (pin "5") (pinfunction "C_5") (pintype "input"))
      (node (ref "U6") (pin "4") (pinfunction "Q2_A_4") (pintype "output"))
    )
    (net (code "67") (name "Net-(U7A-Q4_A)") (class "Default")
      (node (ref "U7") (pin "10") (pinfunction "Q4_A_10") (pintype "output"))
      (node (ref "U7") (pin "15") (pinfunction "DATA_B_15") (pintype "input"))
    )
    (net (code "68") (name "Net-(U8A-J)") (class "Default")
      (node (ref "R7") (pin "1") (pinfunction "1_1") (pintype "passive"))
      (node (ref "U8") (pin "3") (pinfunction "J_3") (pintype "output"))
    )
    (net (code "69") (name "Net-(U9-Pad2)") (class "Default")
      (node (ref "U9") (pin "2") (pinfunction "2_2") (pintype "passive"))
      (node (ref "U9") (pin "3") (pinfunction "3_3") (pintype "passive"))
    )
    (net (code "70") (name "Net-(U10A-Q3A)") (class "Default")
      (node (ref "U10") (pin "5") (pinfunction "Q3A_5") (pintype "output"))
      (node (ref "U12") (pin "5") (pinfunction "A2_5") (pintype "passive"))
    )
    (net (code "71") (name "Net-(U10A-Q4A)") (class "Default")
      (node (ref "U10") (pin "10") (pinfunction "ENB_10") (pintype "input"))
      (node (ref "U10") (pin "6") (pinfunction "Q4A_6") (pintype "output"))
    )
    (net (code "72") (name "Net-(U10B-Q2B)") (class "Default")
      (node (ref "U10") (pin "12") (pinfunction "Q2B_12") (pintype "output"))
      (node (ref "U12") (pin "7") (pinfunction "A1_7") (pintype "passive"))
      (node (ref "U8") (pin "8") (pinfunction "E_8") (pintype "input"))
    )
    (net (code "73") (name "Net-(U11-2)") (class "Default")
      (node (ref "U11") (pin "3") (pinfunction "2_3") (pintype "output"))
      (node (ref "U8") (pin "9") (pinfunction "F_9") (pintype "input"))
    )
    (net (code "74") (name "Net-(U11-3)") (class "Default")
      (node (ref "U11") (pin "15") (pinfunction "RST_15") (pintype "input"))
      (node (ref "U11") (pin "7") (pinfunction "3_7") (pintype "output"))
    )
    (net (code "75") (name "Net-(U12-S1)") (class "Default")
      (node (ref "U12") (pin "10") (pinfunction "S1_10") (pintype "passive"))
      (node (ref "U13") (pin "11") (pinfunction "11_11") (pintype "passive"))
      (node (ref "U14") (pin "11") (pinfunction "11_11") (pintype "passive"))
    )
    (net (code "76") (name "Net-(U12-S2)") (class "Default")
      (node (ref "U12") (pin "11") (pinfunction "S2_11") (pintype "passive"))
      (node (ref "U13") (pin "10") (pinfunction "10_10") (pintype "passive"))
      (node (ref "U14") (pin "10") (pinfunction "10_10") (pintype "passive"))
    )
    (net (code "77") (name "Net-(U12-S3)") (class "Default")
      (node (ref "U12") (pin "12") (pinfunction "S3_12") (pintype "passive"))
      (node (ref "U13") (pin "9") (pinfunction "9_9") (pintype "passive"))
      (node (ref "U14") (pin "9") (pinfunction "9_9") (pintype "passive"))
    )
    (net (code "78") (name "unconnected-(U2A-Q1A-Pad3)") (class "Default")
      (node (ref "U2") (pin "3") (pinfunction "Q1A_3") (pintype "output"))
    )
    (net (code "79") (name "unconnected-(U2A-Q2A-Pad4)") (class "Default")
      (node (ref "U2") (pin "4") (pinfunction "Q2A_4") (pintype "output"))
    )
    (net (code "80") (name "unconnected-(U2A-Q3A-Pad5)") (class "Default")
      (node (ref "U2") (pin "5") (pinfunction "Q3A_5") (pintype "output"))
    )
    (net (code "81") (name "unconnected-(U2B-Q1B-Pad11)") (class "Default")
      (node (ref "U2") (pin "11") (pinfunction "Q1B_11") (pintype "output"))
    )
    (net (code "82") (name "unconnected-(U2B-Q2B-Pad12)") (class "Default")
      (node (ref "U2") (pin "12") (pinfunction "Q2B_12") (pintype "output"))
    )
    (net (code "83") (name "unconnected-(U2B-Q3B-Pad13)") (class "Default")
      (node (ref "U2") (pin "13") (pinfunction "Q3B_13") (pintype "output"))
    )
    (net (code "84") (name "unconnected-(U2B-Q4B-Pad14)") (class "Default")
      (node (ref "U2") (pin "14") (pinfunction "Q4B_14") (pintype "output"))
    )
    (net (code "85") (name "unconnected-(U3A-J-Pad3)") (class "Default")
      (node (ref "U3") (pin "3") (pinfunction "J_3") (pintype "output+no_connect"))
    )
    (net (code "86") (name "unconnected-(U6A-Q1_A-Pad5)") (class "Default")
      (node (ref "U6") (pin "5") (pinfunction "Q1_A_5") (pintype "output"))
    )
    (net (code "87") (name "unconnected-(U6A-Q3_A-Pad3)") (class "Default")
      (node (ref "U6") (pin "3") (pinfunction "Q3_A_3") (pintype "output"))
    )
    (net (code "88") (name "unconnected-(U6A-Q4_A-Pad10)") (class "Default")
      (node (ref "U6") (pin "10") (pinfunction "Q4_A_10") (pintype "output"))
    )
    (net (code "89") (name "unconnected-(U6B-Q1_B-Pad13)") (class "Default")
      (node (ref "U6") (pin "13") (pinfunction "Q1_B_13") (pintype "output"))
    )
    (net (code "90") (name "unconnected-(U6B-Q3_B-Pad11)") (class "Default")
      (node (ref "U6") (pin "11") (pinfunction "Q3_B_11") (pintype "output"))
    )
    (net (code "91") (name "unconnected-(U6B-Q4_B-Pad2)") (class "Default")
      (node (ref "U6") (pin "2") (pinfunction "Q4_B_2") (pintype "output"))
    )
    (net (code "92") (name "unconnected-(U7A-Q1_A-Pad5)") (class "Default")
      (node (ref "U7") (pin "5") (pinfunction "Q1_A_5") (pintype "output"))
    )
    (net (code "93") (name "unconnected-(U7A-Q2_A-Pad4)") (class "Default")
      (node (ref "U7") (pin "4") (pinfunction "Q2_A_4") (pintype "output"))
    )
    (net (code "94") (name "unconnected-(U7A-Q3_A-Pad3)") (class "Default")
      (node (ref "U7") (pin "3") (pinfunction "Q3_A_3") (pintype "output"))
    )
    (net (code "95") (name "unconnected-(U7B-Q1_B-Pad13)") (class "Default")
      (node (ref "U7") (pin "13") (pinfunction "Q1_B_13") (pintype "output"))
    )
    (net (code "96") (name "unconnected-(U7B-Q2_B-Pad12)") (class "Default")
      (node (ref "U7") (pin "12") (pinfunction "Q2_B_12") (pintype "output"))
    )
    (net (code "97") (name "unconnected-(U7B-Q3_B-Pad11)") (class "Default")
      (node (ref "U7") (pin "11") (pinfunction "Q3_B_11") (pintype "output"))
    )
    (net (code "98") (name "unconnected-(U8B-K-Pad4)") (class "Default")
      (node (ref "U8") (pin "4") (pinfunction "K_4") (pintype "output+no_connect"))
    )
    (net (code "99") (name "unconnected-(U10B-Q1B-Pad11)") (class "Default")
      (node (ref "U10") (pin "11") (pinfunction "Q1B_11") (pintype "output"))
    )
    (net (code "100") (name "unconnected-(U11-0-Pad2)") (class "Default")
      (node (ref "U11") (pin "2") (pinfunction "0_2") (pintype "output"))
    )
    (net (code "101") (name "unconnected-(U11-4-Pad11)") (class "Default")
      (node (ref "U11") (pin "11") (pinfunction "4_11") (pintype "output"))
    )
    (net (code "102") (name "unconnected-(U11-5-Pad4)") (class "Default")
      (node (ref "U11") (pin "4") (pinfunction "5_4") (pintype "output"))
    )
    (net (code "103") (name "unconnected-(U11-6-Pad5)") (class "Default")
      (node (ref "U11") (pin "5") (pinfunction "6_5") (pintype "output"))
    )
    (net (code "104") (name "unconnected-(U11-7-Pad10)") (class "Default")
      (node (ref "U11") (pin "10") (pinfunction "7_10") (pintype "output"))
    )
    (net (code "105") (name "unconnected-(U11-CO-Pad12)") (class "Default")
      (node (ref "U11") (pin "12") (pinfunction "CO_12") (pintype "output"))
    )
    (net (code "106") (name "unconnected-(U11-Pad1)") (class "Default")
      (node (ref "U11") (pin "1") (pinfunction "1_1") (pintype "output"))
    )
    (net (code "107") (name "unconnected-(U12-COUT-Pad14)") (class "Default")
      (node (ref "U12") (pin "14") (pinfunction "COUT_14") (pintype "passive+no_connect"))
    )
    (net (code "108") (name "unconnected-(U12-S4-Pad13)") (class "Default")
      (node (ref "U12") (pin "13") (pinfunction "S4_13") (pintype "passive+no_connect"))
    )
  )
)
